# 5G-PreCiSe-SMT100_2023-10-27.net
KiCad netlist of a schematic drawn in EasyEDA
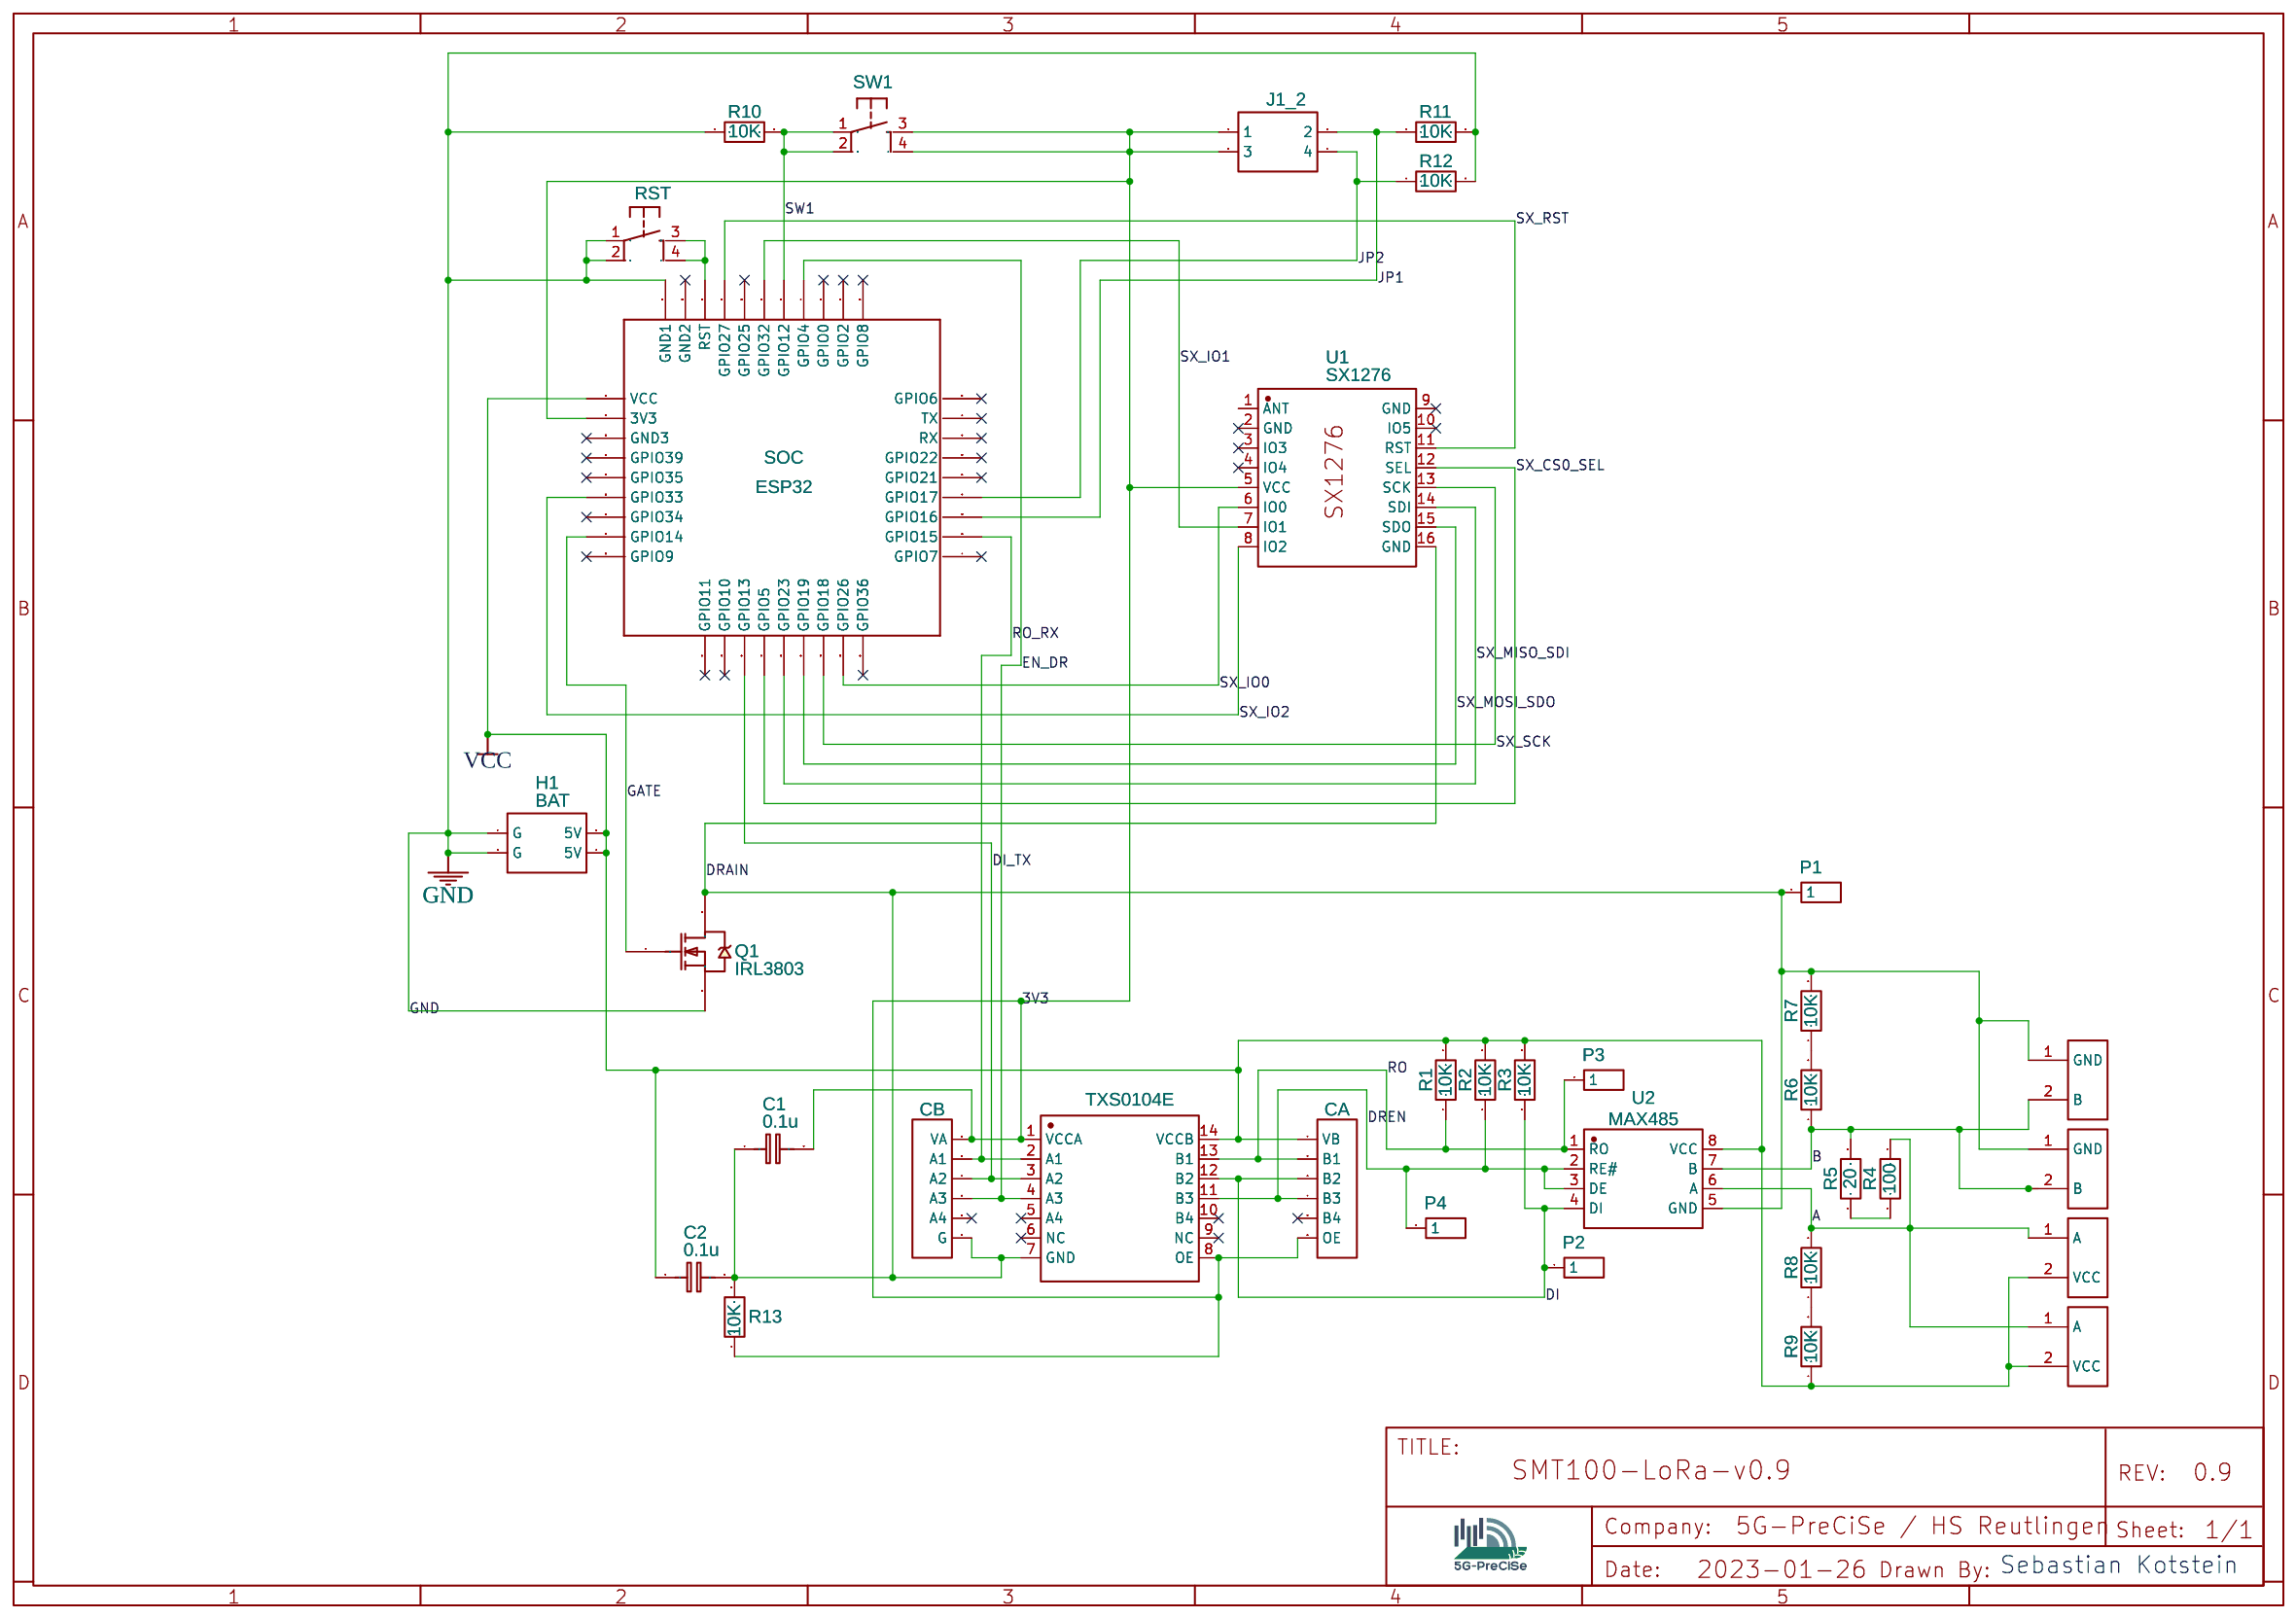
[diagram p0: schematic sheet]

(export (version "E")
  (design (tool "Eeschema 10.0.6"))
  (components
    (comp (ref "C1") (value "0.1u") (libsource (lib "") (part "C_0603_EU")))
    (comp (ref "C2") (value "0.1u") (libsource (lib "") (part "C_0603_EU")))
    (comp (ref "GND_B_0")
      (value "TERMINAL_2P/5.08")
      (fields (field (name "BOM_Manufacturer Part") "Screw terminal 2p"))
      (libsource (lib "") (part "TERMINAL_2P/5.08"))
    )
    (comp (ref "GND_B_1")
      (value "TERMINAL_2P/5.08")
      (fields (field (name "BOM_Manufacturer Part") "Screw terminal 2p"))
      (libsource (lib "") (part "TERMINAL_2P/5.08"))
    )
    (comp (ref "H1")
      (value "BAT")
      (fields (field (name "BOM_Supplier Part") "C239342"))
      (libsource (lib "") (part "HDR-F-2.54_2x2_1"))
    )
    (comp (ref "H2")
      (value "CA")
      (fields (field (name "BOM_Supplier Part") "C40877"))
      (libsource (lib "") (part "HDR-F-2.54_1x6"))
    )
    (comp (ref "H3")
      (value "CB")
      (fields (field (name "BOM_Supplier Part") "C40877"))
      (libsource (lib "") (part "HDR-F-2.54_1x6_1"))
    )
    (comp (ref "H4")
      (value "J1_2")
      (fields (field (name "BOM_Supplier Part") "C239342"))
      (libsource (lib "") (part "HDR-F-2.54_2x2"))
    )
    (comp (ref "J1")
      (value "P1")
      (fields (field (name "BOM_Supplier Part") "C81276"))
      (libsource (lib "") (part "HDR-M-2.54_1x1"))
    )
    (comp (ref "J2")
      (value "P2")
      (fields (field (name "BOM_Supplier Part") "C81276"))
      (libsource (lib "") (part "HDR-M-2.54_1x1"))
    )
    (comp (ref "J3")
      (value "P3")
      (fields (field (name "BOM_Supplier Part") "C81276"))
      (libsource (lib "") (part "HDR-M-2.54_1x1"))
    )
    (comp (ref "J4")
      (value "P4")
      (fields (field (name "BOM_Supplier Part") "C81276"))
      (libsource (lib "") (part "HDR-M-2.54_1x1"))
    )
    (comp (ref "Q1") (value "IRL3803") (libsource (lib "") (part "IRL3803")))
    (comp (ref "R1") (value "10K") (libsource (lib "") (part "R_AXIAL-0.3_EU")))
    (comp (ref "R2") (value "10K") (libsource (lib "") (part "R_AXIAL-0.3_EU")))
    (comp (ref "R3") (value "10K") (libsource (lib "") (part "R_AXIAL-0.3_EU")))
    (comp (ref "R4") (value "100") (libsource (lib "") (part "R_AXIAL-0.3_EU_1")))
    (comp (ref "R5") (value "20") (libsource (lib "") (part "R_AXIAL-0.3_EU")))
    (comp (ref "R6") (value "10K") (libsource (lib "") (part "R_AXIAL-0.3_EU")))
    (comp (ref "R7") (value "10K") (libsource (lib "") (part "R_AXIAL-0.3_EU")))
    (comp (ref "R8") (value "10K") (libsource (lib "") (part "R_AXIAL-0.3_EU")))
    (comp (ref "R9") (value "10K") (libsource (lib "") (part "R_AXIAL-0.3_EU")))
    (comp (ref "R10") (value "10K") (libsource (lib "") (part "R_AXIAL-0.3_EU_2")))
    (comp (ref "R11") (value "10K") (libsource (lib "") (part "R_AXIAL-0.3_EU_2")))
    (comp (ref "R12") (value "10K") (libsource (lib "") (part "R_AXIAL-0.3_EU_2")))
    (comp (ref "R13") (value "10K") (libsource (lib "") (part "R_0603_EU")))
    (comp (ref "S1") (value "RST") (libsource (lib "") (part "TAC_SWITCHPTH")))
    (comp (ref "S2") (value "SW1") (libsource (lib "") (part "TAC_SWITCHPTH")))
    (comp (ref "SOC") (value "ESP32") (libsource (lib "") (part "ESP32-WEMOS-D1-MINI")))
    (comp (ref "U1") (value "SX1276") (libsource (lib "") (part "SX1276_Breakout")))
    (comp (ref "U2")
      (value "MAX485")
      (fields (field (name "BOM_Manufacturer Part") "MAX485CPA+") (field (name "BOM_Supplier Part") "C77792"))
      (libsource (lib "") (part "MAX485CPA+"))
    )
    (comp (ref "U3")
      (value "TXS0104E")
      (fields (field (name "BOM_Manufacturer Part") "TXS0104EDR") (field (name "BOM_Supplier Part") "C79342"))
      (libsource (lib "") (part "TXS0104EDR"))
    )
    (comp (ref "VCC_A_0")
      (value "TERMINAL_2P/5.08")
      (fields (field (name "BOM_Manufacturer Part") "Screw terminal 2p"))
      (libsource (lib "") (part "TERMINAL_2P/5.08_1"))
    )
    (comp (ref "VCC_A_1")
      (value "TERMINAL_2P/5.08")
      (fields (field (name "BOM_Manufacturer Part") "Screw terminal 2p"))
      (libsource (lib "") (part "TERMINAL_2P/5.08_1"))
    )
  )
  (nets
    (net (code "1") (name "/3V3") (class "Default")
      (node (ref "C1") (pin "2") (pinfunction "2_2") (pintype "unspecified"))
      (node (ref "H2") (pin "6") (pinfunction "OE_6") (pintype "input"))
      (node (ref "H3") (pin "6") (pinfunction "VA_6") (pintype "input"))
      (node (ref "H4") (pin "1") (pinfunction "1_1") (pintype "unspecified"))
      (node (ref "H4") (pin "3") (pinfunction "3_3") (pintype "unspecified"))
      (node (ref "R13") (pin "1") (pinfunction "1_1") (pintype "unspecified"))
      (node (ref "S2") (pin "3") (pinfunction "3_3") (pintype "bidirectional"))
      (node (ref "S2") (pin "4") (pinfunction "4_4") (pintype "bidirectional"))
      (node (ref "SOC") (pin "3V3") (pinfunction "3V3_3V3") (pintype "bidirectional"))
      (node (ref "U1") (pin "5") (pinfunction "VCC_5") (pintype "unspecified"))
      (node (ref "U3") (pin "1") (pinfunction "VCCA_1") (pintype "unspecified"))
      (node (ref "U3") (pin "8") (pinfunction "OE_8") (pintype "unspecified"))
    )
    (net (code "2") (name "/A") (class "Default")
      (node (ref "R4") (pin "1") (pinfunction "1_1") (pintype "unspecified"))
      (node (ref "R8") (pin "2") (pinfunction "2_2") (pintype "unspecified"))
      (node (ref "U2") (pin "6") (pinfunction "A_6") (pintype "unspecified"))
      (node (ref "VCC_A_0") (pin "1") (pinfunction "A_1") (pintype "unspecified"))
      (node (ref "VCC_A_1") (pin "1") (pinfunction "A_1") (pintype "unspecified"))
    )
    (net (code "3") (name "/B") (class "Default")
      (node (ref "GND_B_0") (pin "2") (pinfunction "B_2") (pintype "unspecified"))
      (node (ref "GND_B_1") (pin "2") (pinfunction "B_2") (pintype "unspecified"))
      (node (ref "R5") (pin "2") (pinfunction "2_2") (pintype "unspecified"))
      (node (ref "R6") (pin "1") (pinfunction "1_1") (pintype "unspecified"))
      (node (ref "U2") (pin "7") (pinfunction "B_7") (pintype "unspecified"))
    )
    (net (code "4") (name "/DI") (class "Default")
      (node (ref "H2") (pin "3") (pinfunction "B2_3") (pintype "input"))
      (node (ref "J2") (pin "1") (pinfunction "1_1") (pintype "input"))
      (node (ref "R3") (pin "1") (pinfunction "1_1") (pintype "unspecified"))
      (node (ref "U2") (pin "4") (pinfunction "DI_4") (pintype "unspecified"))
      (node (ref "U3") (pin "12") (pinfunction "B2_12") (pintype "unspecified"))
    )
    (net (code "5") (name "/DI_TX") (class "Default")
      (node (ref "H3") (pin "4") (pinfunction "A2_4") (pintype "input"))
      (node (ref "SOC") (pin "13") (pinfunction "GPIO13_13") (pintype "bidirectional"))
      (node (ref "U3") (pin "3") (pinfunction "A2_3") (pintype "unspecified"))
    )
    (net (code "6") (name "/DRAIN") (class "Default")
      (node (ref "C1") (pin "1") (pinfunction "1_1") (pintype "unspecified"))
      (node (ref "C2") (pin "2") (pinfunction "2_2") (pintype "unspecified"))
      (node (ref "GND_B_0") (pin "1") (pinfunction "GND_1") (pintype "unspecified"))
      (node (ref "GND_B_1") (pin "1") (pinfunction "GND_1") (pintype "unspecified"))
      (node (ref "H3") (pin "1") (pinfunction "G_1") (pintype "input"))
      (node (ref "J1") (pin "1") (pinfunction "1_1") (pintype "input"))
      (node (ref "Q1") (pin "2") (pinfunction "D_2") (pintype "unspecified"))
      (node (ref "R13") (pin "2") (pinfunction "2_2") (pintype "unspecified"))
      (node (ref "R7") (pin "2") (pinfunction "2_2") (pintype "unspecified"))
      (node (ref "U1") (pin "16") (pinfunction "GND_16") (pintype "unspecified"))
      (node (ref "U2") (pin "5") (pinfunction "GND_5") (pintype "unspecified"))
      (node (ref "U3") (pin "7") (pinfunction "GND_7") (pintype "unspecified"))
    )
    (net (code "7") (name "/DREN") (class "Default")
      (node (ref "H2") (pin "4") (pinfunction "B3_4") (pintype "input"))
      (node (ref "J4") (pin "1") (pinfunction "1_1") (pintype "input"))
      (node (ref "R2") (pin "1") (pinfunction "1_1") (pintype "unspecified"))
      (node (ref "U2") (pin "2") (pinfunction "RE#_2") (pintype "unspecified"))
      (node (ref "U2") (pin "3") (pinfunction "DE_3") (pintype "unspecified"))
      (node (ref "U3") (pin "11") (pinfunction "B3_11") (pintype "unspecified"))
    )
    (net (code "8") (name "/EN_DR") (class "Default")
      (node (ref "H3") (pin "3") (pinfunction "A3_3") (pintype "input"))
      (node (ref "SOC") (pin "4") (pinfunction "GPIO4_4") (pintype "bidirectional"))
      (node (ref "U3") (pin "4") (pinfunction "A3_4") (pintype "unspecified"))
    )
    (net (code "9") (name "/GATE") (class "Default")
      (node (ref "Q1") (pin "1") (pinfunction "G_1") (pintype "unspecified"))
      (node (ref "SOC") (pin "14") (pinfunction "GPIO14_14") (pintype "bidirectional"))
    )
    (net (code "10") (name "/JP1") (class "Default")
      (node (ref "H4") (pin "2") (pinfunction "2_2") (pintype "unspecified"))
      (node (ref "R11") (pin "1") (pinfunction "1_1") (pintype "unspecified"))
      (node (ref "SOC") (pin "16") (pinfunction "GPIO16_16") (pintype "bidirectional"))
    )
    (net (code "11") (name "/JP2") (class "Default")
      (node (ref "H4") (pin "4") (pinfunction "4_4") (pintype "unspecified"))
      (node (ref "R12") (pin "1") (pinfunction "1_1") (pintype "unspecified"))
      (node (ref "SOC") (pin "17") (pinfunction "GPIO17_17") (pintype "bidirectional"))
    )
    (net (code "12") (name "/RO") (class "Default")
      (node (ref "H2") (pin "2") (pinfunction "B1_2") (pintype "input"))
      (node (ref "J3") (pin "1") (pinfunction "1_1") (pintype "input"))
      (node (ref "R1") (pin "1") (pinfunction "1_1") (pintype "unspecified"))
      (node (ref "U2") (pin "1") (pinfunction "RO_1") (pintype "unspecified"))
      (node (ref "U3") (pin "13") (pinfunction "B1_13") (pintype "unspecified"))
    )
    (net (code "13") (name "/RO_RX") (class "Default")
      (node (ref "H3") (pin "5") (pinfunction "A1_5") (pintype "input"))
      (node (ref "SOC") (pin "15") (pinfunction "GPIO15_15") (pintype "bidirectional"))
      (node (ref "U3") (pin "2") (pinfunction "A1_2") (pintype "unspecified"))
    )
    (net (code "14") (name "/SW1") (class "Default")
      (node (ref "R10") (pin "2") (pinfunction "2_2") (pintype "unspecified"))
      (node (ref "S2") (pin "1") (pinfunction "1_1") (pintype "bidirectional"))
      (node (ref "S2") (pin "2") (pinfunction "2_2") (pintype "bidirectional"))
      (node (ref "SOC") (pin "12") (pinfunction "GPIO12_12") (pintype "bidirectional"))
    )
    (net (code "15") (name "/SX_CS0_SEL") (class "Default")
      (node (ref "SOC") (pin "5") (pinfunction "GPIO5_5") (pintype "bidirectional"))
      (node (ref "U1") (pin "12") (pinfunction "SEL_12") (pintype "unspecified"))
    )
    (net (code "16") (name "/SX_IO0") (class "Default")
      (node (ref "SOC") (pin "26") (pinfunction "GPIO26_26") (pintype "bidirectional"))
      (node (ref "U1") (pin "6") (pinfunction "IO0_6") (pintype "unspecified"))
    )
    (net (code "17") (name "/SX_IO1") (class "Default")
      (node (ref "SOC") (pin "32") (pinfunction "GPIO32_32") (pintype "bidirectional"))
      (node (ref "U1") (pin "7") (pinfunction "IO1_7") (pintype "unspecified"))
    )
    (net (code "18") (name "/SX_IO2") (class "Default")
      (node (ref "SOC") (pin "33") (pinfunction "GPIO33_33") (pintype "bidirectional"))
      (node (ref "U1") (pin "8") (pinfunction "IO2_8") (pintype "unspecified"))
    )
    (net (code "19") (name "/SX_MISO_SDI") (class "Default")
      (node (ref "SOC") (pin "23") (pinfunction "GPIO23_23") (pintype "bidirectional"))
      (node (ref "U1") (pin "14") (pinfunction "SDI_14") (pintype "unspecified"))
    )
    (net (code "20") (name "/SX_MOSI_SDO") (class "Default")
      (node (ref "SOC") (pin "19") (pinfunction "GPIO19_19") (pintype "bidirectional"))
      (node (ref "U1") (pin "15") (pinfunction "SDO_15") (pintype "unspecified"))
    )
    (net (code "21") (name "/SX_RST") (class "Default")
      (node (ref "SOC") (pin "27") (pinfunction "GPIO27_27") (pintype "bidirectional"))
      (node (ref "U1") (pin "11") (pinfunction "RST_11") (pintype "unspecified"))
    )
    (net (code "22") (name "/SX_SCK") (class "Default")
      (node (ref "SOC") (pin "18") (pinfunction "GPIO18_18") (pintype "bidirectional"))
      (node (ref "U1") (pin "13") (pinfunction "SCK_13") (pintype "unspecified"))
    )
    (net (code "23") (name "GND") (class "Default")
      (node (ref "H1") (pin "1") (pinfunction "G_1") (pintype "unspecified"))
      (node (ref "H1") (pin "3") (pinfunction "G_3") (pintype "unspecified"))
      (node (ref "Q1") (pin "3") (pinfunction "S_3") (pintype "unspecified"))
      (node (ref "R10") (pin "1") (pinfunction "1_1") (pintype "unspecified"))
      (node (ref "R11") (pin "2") (pinfunction "2_2") (pintype "unspecified"))
      (node (ref "R12") (pin "2") (pinfunction "2_2") (pintype "unspecified"))
      (node (ref "S1") (pin "1") (pinfunction "1_1") (pintype "bidirectional"))
      (node (ref "S1") (pin "2") (pinfunction "2_2") (pintype "bidirectional"))
      (node (ref "SOC") (pin "GND1") (pinfunction "GND1_GND1") (pintype "bidirectional"))
    )
    (net (code "24") (name "Net-(R4-Pad2)") (class "Default")
      (node (ref "R4") (pin "2") (pinfunction "2_2") (pintype "unspecified"))
      (node (ref "R5") (pin "1") (pinfunction "1_1") (pintype "unspecified"))
    )
    (net (code "25") (name "Net-(R6-Pad2)") (class "Default")
      (node (ref "R6") (pin "2") (pinfunction "2_2") (pintype "unspecified"))
      (node (ref "R7") (pin "1") (pinfunction "1_1") (pintype "unspecified"))
    )
    (net (code "26") (name "Net-(R8-Pad1)") (class "Default")
      (node (ref "R8") (pin "1") (pinfunction "1_1") (pintype "unspecified"))
      (node (ref "R9") (pin "2") (pinfunction "2_2") (pintype "unspecified"))
    )
    (net (code "27") (name "Net-(S1-Pad3)") (class "Default")
      (node (ref "S1") (pin "3") (pinfunction "3_3") (pintype "bidirectional"))
      (node (ref "S1") (pin "4") (pinfunction "4_4") (pintype "bidirectional"))
      (node (ref "SOC") (pin "RST") (pinfunction "RST_RST") (pintype "bidirectional"))
    )
    (net (code "28") (name "VCC") (class "Default")
      (node (ref "C2") (pin "1") (pinfunction "1_1") (pintype "unspecified"))
      (node (ref "H1") (pin "2") (pinfunction "5V_2") (pintype "unspecified"))
      (node (ref "H1") (pin "4") (pinfunction "5V_4") (pintype "unspecified"))
      (node (ref "H2") (pin "1") (pinfunction "VB_1") (pintype "input"))
      (node (ref "R1") (pin "2") (pinfunction "2_2") (pintype "unspecified"))
      (node (ref "R2") (pin "2") (pinfunction "2_2") (pintype "unspecified"))
      (node (ref "R3") (pin "2") (pinfunction "2_2") (pintype "unspecified"))
      (node (ref "R9") (pin "1") (pinfunction "1_1") (pintype "unspecified"))
      (node (ref "SOC") (pin "VCC") (pinfunction "VCC_VCC") (pintype "bidirectional"))
      (node (ref "U2") (pin "8") (pinfunction "VCC_8") (pintype "unspecified"))
      (node (ref "U3") (pin "14") (pinfunction "VCCB_14") (pintype "unspecified"))
      (node (ref "VCC_A_0") (pin "2") (pinfunction "VCC_2") (pintype "unspecified"))
      (node (ref "VCC_A_1") (pin "2") (pinfunction "VCC_2") (pintype "unspecified"))
    )
    (net (code "29") (name "unconnected-(H2-B4-Pad5)") (class "Default")
      (node (ref "H2") (pin "5") (pinfunction "B4_5") (pintype "input+no_connect"))
    )
    (net (code "30") (name "unconnected-(H3-A4-Pad2)") (class "Default")
      (node (ref "H3") (pin "2") (pinfunction "A4_2") (pintype "input+no_connect"))
    )
    (net (code "31") (name "unconnected-(SOC-GPIO0-Pad0)") (class "Default")
      (node (ref "SOC") (pin "0") (pinfunction "GPIO0_0") (pintype "bidirectional+no_connect"))
    )
    (net (code "32") (name "unconnected-(SOC-GPIO2-Pad2)") (class "Default")
      (node (ref "SOC") (pin "2") (pinfunction "GPIO2_2") (pintype "bidirectional+no_connect"))
    )
    (net (code "33") (name "unconnected-(SOC-GPIO6-Pad6)") (class "Default")
      (node (ref "SOC") (pin "6") (pinfunction "GPIO6_6") (pintype "bidirectional+no_connect"))
    )
    (net (code "34") (name "unconnected-(SOC-GPIO7-Pad7)") (class "Default")
      (node (ref "SOC") (pin "7") (pinfunction "GPIO7_7") (pintype "bidirectional+no_connect"))
    )
    (net (code "35") (name "unconnected-(SOC-GPIO8-Pad8)") (class "Default")
      (node (ref "SOC") (pin "8") (pinfunction "GPIO8_8") (pintype "bidirectional+no_connect"))
    )
    (net (code "36") (name "unconnected-(SOC-GPIO9-Pad9)") (class "Default")
      (node (ref "SOC") (pin "9") (pinfunction "GPIO9_9") (pintype "bidirectional+no_connect"))
    )
    (net (code "37") (name "unconnected-(SOC-GPIO10-Pad10)") (class "Default")
      (node (ref "SOC") (pin "10") (pinfunction "GPIO10_10") (pintype "bidirectional+no_connect"))
    )
    (net (code "38") (name "unconnected-(SOC-GPIO11-Pad11)") (class "Default")
      (node (ref "SOC") (pin "11") (pinfunction "GPIO11_11") (pintype "bidirectional+no_connect"))
    )
    (net (code "39") (name "unconnected-(SOC-GPIO21-Pad21)") (class "Default")
      (node (ref "SOC") (pin "21") (pinfunction "GPIO21_21") (pintype "bidirectional+no_connect"))
    )
    (net (code "40") (name "unconnected-(SOC-GPIO22-Pad22)") (class "Default")
      (node (ref "SOC") (pin "22") (pinfunction "GPIO22_22") (pintype "bidirectional+no_connect"))
    )
    (net (code "41") (name "unconnected-(SOC-GPIO25-Pad25)") (class "Default")
      (node (ref "SOC") (pin "25") (pinfunction "GPIO25_25") (pintype "bidirectional+no_connect"))
    )
    (net (code "42") (name "unconnected-(SOC-GPIO34-Pad34)") (class "Default")
      (node (ref "SOC") (pin "34") (pinfunction "GPIO34_34") (pintype "bidirectional+no_connect"))
    )
    (net (code "43") (name "unconnected-(SOC-GPIO35-Pad35)") (class "Default")
      (node (ref "SOC") (pin "35") (pinfunction "GPIO35_35") (pintype "bidirectional+no_connect"))
    )
    (net (code "44") (name "unconnected-(SOC-GPIO36-Pad36)") (class "Default")
      (node (ref "SOC") (pin "36") (pinfunction "GPIO36_36") (pintype "bidirectional+no_connect"))
    )
    (net (code "45") (name "unconnected-(SOC-GPIO39-Pad39)") (class "Default")
      (node (ref "SOC") (pin "39") (pinfunction "GPIO39_39") (pintype "bidirectional+no_connect"))
    )
    (net (code "46") (name "unconnected-(SOC-PadGND2)") (class "Default")
      (node (ref "SOC") (pin "GND2") (pinfunction "GND2_GND2") (pintype "bidirectional+no_connect"))
    )
    (net (code "47") (name "unconnected-(SOC-PadGND3)") (class "Default")
      (node (ref "SOC") (pin "GND3") (pinfunction "GND3_GND3") (pintype "bidirectional+no_connect"))
    )
    (net (code "48") (name "unconnected-(SOC-PadRX)") (class "Default")
      (node (ref "SOC") (pin "RX") (pinfunction "RX_RX") (pintype "bidirectional+no_connect"))
    )
    (net (code "49") (name "unconnected-(SOC-PadTX)") (class "Default")
      (node (ref "SOC") (pin "TX") (pinfunction "TX_TX") (pintype "bidirectional+no_connect"))
    )
    (net (code "50") (name "unconnected-(U1-ANT-Pad1)") (class "Default")
      (node (ref "U1") (pin "1") (pinfunction "ANT_1") (pintype "unspecified"))
    )
    (net (code "51") (name "unconnected-(U1-GND-Pad2)") (class "Default")
      (node (ref "U1") (pin "2") (pinfunction "GND_2") (pintype "unspecified+no_connect"))
    )
    (net (code "52") (name "unconnected-(U1-GND-Pad9)") (class "Default")
      (node (ref "U1") (pin "9") (pinfunction "GND_9") (pintype "unspecified+no_connect"))
    )
    (net (code "53") (name "unconnected-(U1-IO3-Pad3)") (class "Default")
      (node (ref "U1") (pin "3") (pinfunction "IO3_3") (pintype "unspecified+no_connect"))
    )
    (net (code "54") (name "unconnected-(U1-IO4-Pad4)") (class "Default")
      (node (ref "U1") (pin "4") (pinfunction "IO4_4") (pintype "unspecified+no_connect"))
    )
    (net (code "55") (name "unconnected-(U1-IO5-Pad10)") (class "Default")
      (node (ref "U1") (pin "10") (pinfunction "IO5_10") (pintype "unspecified+no_connect"))
    )
    (net (code "56") (name "unconnected-(U3-A4-Pad5)") (class "Default")
      (node (ref "U3") (pin "5") (pinfunction "A4_5") (pintype "unspecified+no_connect"))
    )
    (net (code "57") (name "unconnected-(U3-B4-Pad10)") (class "Default")
      (node (ref "U3") (pin "10") (pinfunction "B4_10") (pintype "unspecified+no_connect"))
    )
    (net (code "58") (name "unconnected-(U3-NC-Pad6)") (class "Default")
      (node (ref "U3") (pin "6") (pinfunction "NC_6") (pintype "unspecified+no_connect"))
    )
    (net (code "59") (name "unconnected-(U3-NC-Pad9)") (class "Default")
      (node (ref "U3") (pin "9") (pinfunction "NC_9") (pintype "unspecified+no_connect"))
    )
  )
)
